# eVV_Main_Controller.net
KiCad netlist of a schematic drawn in Altium Designer
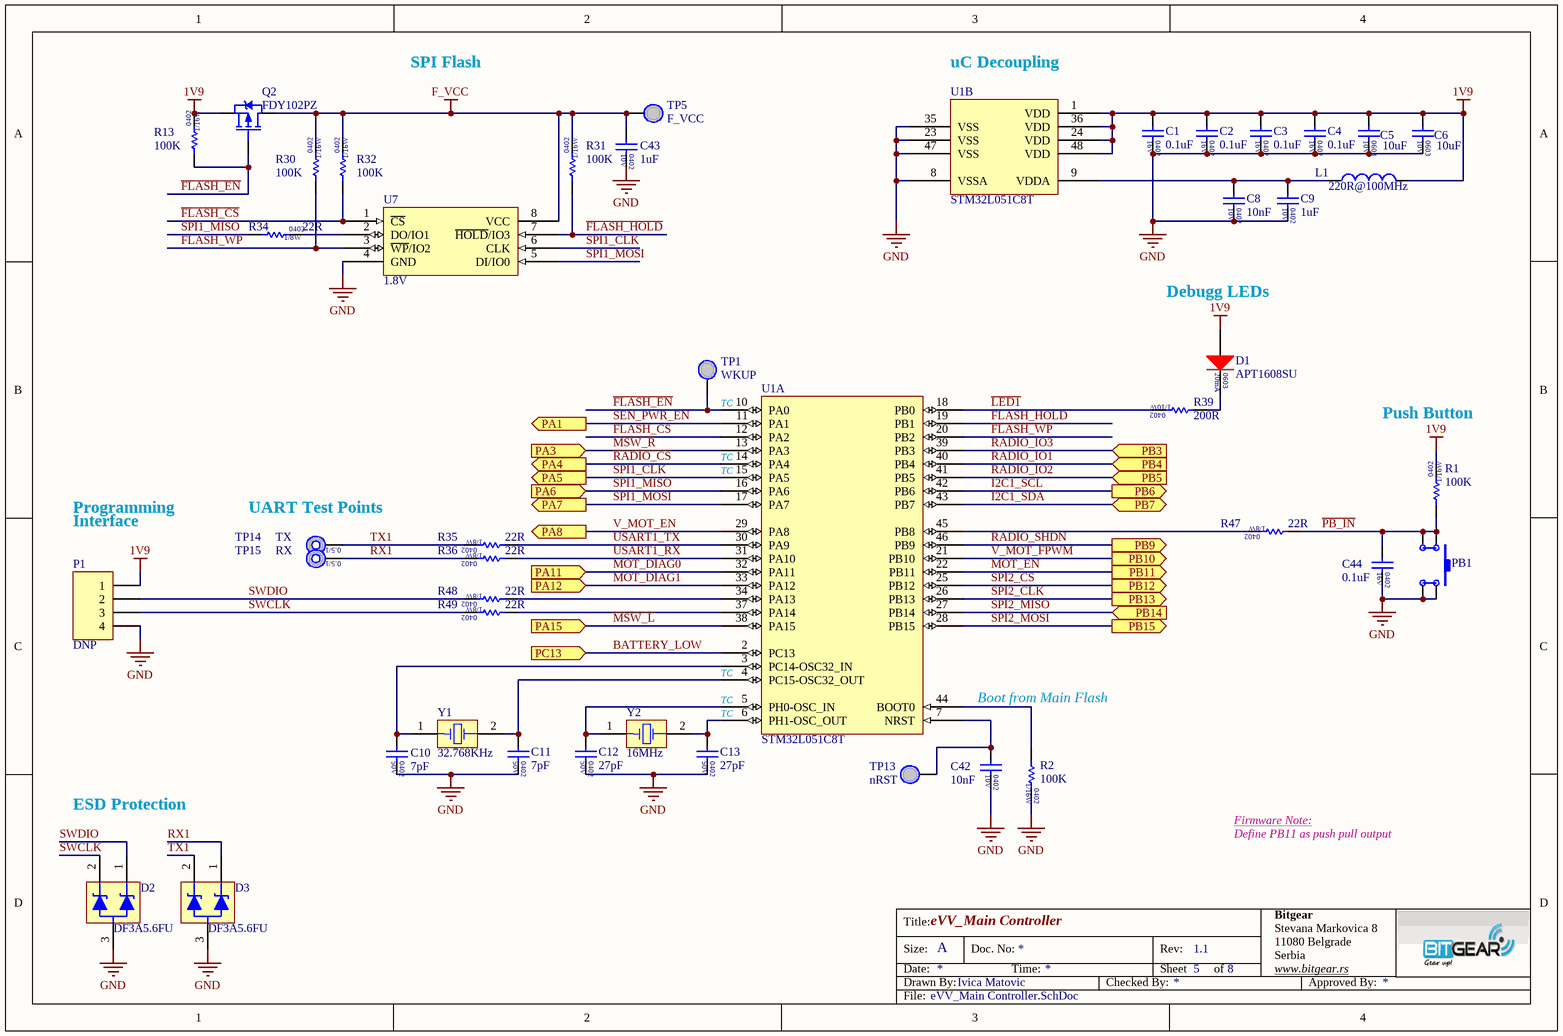
[diagram p0: eVV_Main Controller.SchDoc]

(export (version "E")
  (design (tool "Eeschema 10.0.6"))
  (components
    (comp (ref "C1")
      (value "0.1uF")
      (footprint "CAPC1005X60N")
      (description "CAP CER 0.1UF 0402 (1005) 16V X7R 10%")
      (fields (field (name "MANUFACTURER") "Murata Electronics North America"))
      (libsource (lib "ecoVENTV") (part "Cap-1005 (0402) CER 0.1UF 16V X7R 10%"))
    )
    (comp (ref "C2")
      (value "0.1uF")
      (footprint "CAPC1005X60N")
      (description "CAP CER 0.1UF 0402 (1005) 16V X7R 10%")
      (fields (field (name "MANUFACTURER") "Murata Electronics North America"))
      (libsource (lib "ecoVENTV") (part "Cap-1005 (0402) CER 0.1UF 16V X7R 10%"))
    )
    (comp (ref "C3")
      (value "0.1uF")
      (footprint "CAPC1005X60N")
      (description "CAP CER 0.1UF 0402 (1005) 16V X7R 10%")
      (fields (field (name "MANUFACTURER") "Murata Electronics North America"))
      (libsource (lib "ecoVENTV") (part "Cap-1005 (0402) CER 0.1UF 16V X7R 10%"))
    )
    (comp (ref "C4")
      (value "0.1uF")
      (footprint "CAPC1005X60N")
      (description "CAP CER 0.1UF 0402 (1005) 16V X7R 10%")
      (fields (field (name "MANUFACTURER") "Murata Electronics North America"))
      (libsource (lib "ecoVENTV") (part "Cap-1005 (0402) CER 0.1UF 16V X7R 10%"))
    )
    (comp (ref "C5")
      (value "10uF")
      (footprint "CAPC1608X95N")
      (description "Capacitor Ceramic 10uF 1608 (0603) 10V X5R 20%")
      (fields (field (name "MANUFACTURER") "Taiyo Yuden"))
      (libsource (lib "ecoVENTV") (part "Cap-1608 (0603) CER 10uF 10V X5R 20%"))
    )
    (comp (ref "C6")
      (value "10uF")
      (footprint "CAPC1608X95N")
      (description "Capacitor Ceramic 10uF 1608 (0603) 10V X5R 20%")
      (fields (field (name "MANUFACTURER") "Taiyo Yuden"))
      (libsource (lib "ecoVENTV") (part "Cap-1608 (0603) CER 10uF 10V X5R 20%"))
    )
    (comp (ref "C8")
      (value "10nF")
      (footprint "CAPC1005X60N")
      (description "Cap-1005 (0402) CER 10nF 10V X7R 10%")
      (fields (field (name "MANUFACTURER") "Samsung"))
      (libsource (lib "ecoVENTV") (part "Cap-1005 (0402) CER 10nF 10V X7R 10%"))
    )
    (comp (ref "C9")
      (value "1uF")
      (footprint "CAPC1005X60N")
      (description "Cap-1005 (0402) CER 1uF 10V X5R 10%")
      (fields (field (name "MANUFACTURER") "Murata Electronics North America"))
      (libsource (lib "ecoVENTV") (part "Cap-1005 (0402) CER 1uF 10V X5R 10%"))
    )
    (comp (ref "C10")
      (value "7pF")
      (footprint "CAPC1005X60N")
      (description "Cap-1005 (0402) CER 7pF 50V C0G 0.5pF")
      (fields (field (name "MANUFACTURER") "Murata Electronics North America"))
      (libsource (lib "ecoVENTV") (part "Cap-1005 (0402) CER 7pF 50V C0G 0.5pF"))
    )
    (comp (ref "C11")
      (value "7pF")
      (footprint "CAPC1005X60N")
      (description "Cap-1005 (0402) CER 7pF 50V C0G 0.5pF")
      (fields (field (name "MANUFACTURER") "Murata Electronics North America"))
      (libsource (lib "ecoVENTV") (part "Cap-1005 (0402) CER 7pF 50V C0G 0.5pF"))
    )
    (comp (ref "C12")
      (value "27pF")
      (footprint "CAPC1005X60N")
      (description "CAP CER 27PF 50V 5% NP0 0402 (1005)")
      (fields (field (name "MANUFACTURER") "Murata Electronics North America"))
      (libsource (lib "ecoVENTV") (part "Cap-1005 (0402) CER 27pF 50V NP0 5%"))
    )
    (comp (ref "C13")
      (value "27pF")
      (footprint "CAPC1005X60N")
      (description "CAP CER 27PF 50V 5% NP0 0402 (1005)")
      (fields (field (name "MANUFACTURER") "Murata Electronics North America"))
      (libsource (lib "ecoVENTV") (part "Cap-1005 (0402) CER 27pF 50V NP0 5%"))
    )
    (comp (ref "C42")
      (value "10nF")
      (footprint "CAPC1005X60N")
      (description "Cap-1005 (0402) CER 10nF 10V X7R 10%")
      (fields (field (name "MANUFACTURER") "Samsung"))
      (libsource (lib "ecoVENTV") (part "Cap-1005 (0402) CER 10nF 10V X7R 10%"))
    )
    (comp (ref "C43")
      (value "1uF")
      (footprint "CAPC1005X60N")
      (description "Cap-1005 (0402) CER 1uF 10V X5R 10%")
      (fields (field (name "MANUFACTURER") "Murata Electronics North America"))
      (libsource (lib "ecoVENTV") (part "Cap-1005 (0402) CER 1uF 10V X5R 10%"))
    )
    (comp (ref "C44")
      (value "0.1uF")
      (footprint "CAPC1005X60N")
      (description "CAP CER 0.1UF 0402 (1005) 16V X7R 10%")
      (fields (field (name "MANUFACTURER") "Murata Electronics North America"))
      (libsource (lib "ecoVENTV") (part "Cap-1005 (0402) CER 0.1UF 16V X7R 10%"))
    )
    (comp (ref "D1")
      (value "APT1608SU")
      (footprint "DIOC1608X84N_R")
      (description "LED Red 0603 20mA")
      (fields (field (name "MANUFACTURER") "Kingbright"))
      (libsource (lib "ecoVENTV") (part "APT1608SU"))
    )
    (comp (ref "D2")
      (value "DF3A5.6FU")
      (footprint "SOT65P210X110-3N")
      (description "30kV ESD Protection Diode, Vr=2.5V, Vz=5.6V, Ilkg=1uA")
      (fields (field (name "MANUFACTURER") "Toshiba Semiconductor"))
      (libsource (lib "ecoVENTV") (part "DF3A5.6FU"))
    )
    (comp (ref "D3")
      (value "DF3A5.6FU")
      (footprint "SOT65P210X110-3N")
      (description "30kV ESD Protection Diode, Vr=2.5V, Vz=5.6V, Ilkg=1uA")
      (fields (field (name "MANUFACTURER") "Toshiba Semiconductor"))
      (libsource (lib "ecoVENTV") (part "DF3A5.6FU"))
    )
    (comp (ref "L1")
      (value "220R@100MHz")
      (footprint "INDC1005X60N")
      (description "FERRITE BEAD 220 Ohm 800mA 0402")
      (fields (field (name "MANUFACTURER") "Taiyo Yuden"))
      (libsource (lib "ecoVENTV") (part "FBead-1005 (0402) 220 Ohm 800mA"))
    )
    (comp (ref "P1")
      (value "DNP")
      (footprint "HDR1X4_100MIL")
      (description "Header, 4-Pin")
      (libsource (lib "ecoVENTV") (part "Header 4"))
    )
    (comp (ref "PB1")
      (value "switch")
      (footprint "CK_KMR221NG")
      (description "Push Button SPST-NO 4.6X2.8mm")
      (fields (field (name "MANUFACTURER") "C&K Components"))
      (libsource (lib "ecoVENTV") (part "KMR221NG"))
    )
    (comp (ref "Q2")
      (value "FDY102PZ")
      (footprint "SOT50P160X78-3N")
      (description "P-MOSFET Single 0.83A Low Vgs")
      (fields (field (name "MANUFACTURER") "Fairchild"))
      (libsource (lib "ecoVENTV") (part "FDY102PZ"))
    )
    (comp (ref "R1")
      (value "100K")
      (footprint "RESC1005X40AN")
      (description "Res-1005 (0402) 100 KOhm 1/16W 1%")
      (fields (field (name "MANUFACTURER") "Vishay Dale"))
      (libsource (lib "ecoVENTV") (part "Res-1005 (0402) 100 KOhm 1/16W 1%"))
    )
    (comp (ref "R2")
      (value "100K")
      (footprint "RESC1005X40AN")
      (description "Res-1005 (0402) 100 KOhm 1/16W 1%")
      (fields (field (name "MANUFACTURER") "Vishay Dale"))
      (libsource (lib "ecoVENTV") (part "Res-1005 (0402) 100 KOhm 1/16W 1%"))
    )
    (comp (ref "R13")
      (value "100K")
      (footprint "RESC1005X40AN")
      (description "Res-1005 (0402) 100 KOhm 1/16W 1%")
      (fields (field (name "MANUFACTURER") "Vishay Dale"))
      (libsource (lib "ecoVENTV") (part "Res-1005 (0402) 100 KOhm 1/16W 1%"))
    )
    (comp (ref "R30")
      (value "100K")
      (footprint "RESC1005X40AN")
      (description "Res-1005 (0402) 100 KOhm 1/16W 1%")
      (fields (field (name "MANUFACTURER") "Vishay Dale"))
      (libsource (lib "ecoVENTV") (part "Res-1005 (0402) 100 KOhm 1/16W 1%"))
    )
    (comp (ref "R31")
      (value "100K")
      (footprint "RESC1005X40AN")
      (description "Res-1005 (0402) 100 KOhm 1/16W 1%")
      (fields (field (name "MANUFACTURER") "Vishay Dale"))
      (libsource (lib "ecoVENTV") (part "Res-1005 (0402) 100 KOhm 1/16W 1%"))
    )
    (comp (ref "R32")
      (value "100K")
      (footprint "RESC1005X40AN")
      (description "Res-1005 (0402) 100 KOhm 1/16W 1%")
      (fields (field (name "MANUFACTURER") "Vishay Dale"))
      (libsource (lib "ecoVENTV") (part "Res-1005 (0402) 100 KOhm 1/16W 1%"))
    )
    (comp (ref "R34")
      (value "22R")
      (footprint "RESC1005X40AN")
      (description "Res-1005 (0402) 22 Ohm 1/8W 1%")
      (fields (field (name "MANUFACTURER") "Vishay Dale"))
      (libsource (lib "ecoVENTV") (part "Res-1005 (0402) 22 Ohm 1/8W 1%"))
    )
    (comp (ref "R35")
      (value "22R")
      (footprint "RESC1005X40AN")
      (description "Res-1005 (0402) 22 Ohm 1/8W 1%")
      (fields (field (name "MANUFACTURER") "Vishay Dale"))
      (libsource (lib "ecoVENTV") (part "Res-1005 (0402) 22 Ohm 1/8W 1%"))
    )
    (comp (ref "R36")
      (value "22R")
      (footprint "RESC1005X40AN")
      (description "Res-1005 (0402) 22 Ohm 1/8W 1%")
      (fields (field (name "MANUFACTURER") "Vishay Dale"))
      (libsource (lib "ecoVENTV") (part "Res-1005 (0402) 22 Ohm 1/8W 1%"))
    )
    (comp (ref "R39")
      (value "200R")
      (footprint "RESC1005X40AN")
      (description "Res-1005 (0402) 200 Ohm 1/10W 5%")
      (fields (field (name "MANUFACTURER") "Vishay Dale"))
      (libsource (lib "ecoVENTV") (part "Res-1005 (0402) 200 Ohm 1/10W 5%"))
    )
    (comp (ref "R47")
      (value "22R")
      (footprint "RESC1005X40AN")
      (description "Res-1005 (0402) 22 Ohm 1/8W 1%")
      (fields (field (name "MANUFACTURER") "Vishay Dale"))
      (libsource (lib "ecoVENTV") (part "Res-1005 (0402) 22 Ohm 1/8W 1%"))
    )
    (comp (ref "R48")
      (value "22R")
      (footprint "RESC1005X40AN")
      (description "Res-1005 (0402) 22 Ohm 1/8W 1%")
      (fields (field (name "MANUFACTURER") "Vishay Dale"))
      (libsource (lib "ecoVENTV") (part "Res-1005 (0402) 22 Ohm 1/8W 1%"))
    )
    (comp (ref "R49")
      (value "22R")
      (footprint "RESC1005X40AN")
      (description "Res-1005 (0402) 22 Ohm 1/8W 1%")
      (fields (field (name "MANUFACTURER") "Vishay Dale"))
      (libsource (lib "ecoVENTV") (part "Res-1005 (0402) 22 Ohm 1/8W 1%"))
    )
    (comp (ref "TP1")
      (value "WKUP")
      (footprint "TEST_POINT_1MM")
      (description "Test point")
      (libsource (lib "ecoVENTV") (part "TP"))
    )
    (comp (ref "TP5")
      (value "F_VCC")
      (footprint "TEST_POINT_1MM")
      (description "Test point")
      (libsource (lib "") (part "TP_2"))
    )
    (comp (ref "TP13")
      (value "nRST")
      (footprint "TEST_POINT_1MM")
      (description "Test point")
      (libsource (lib "") (part "TP_1"))
    )
    (comp (ref "TP14")
      (value "TX")
      (footprint "TEST_POINT_TH_1MM")
      (description "Test point Through Hole")
      (libsource (lib "ecoVENTV") (part "TP TH"))
    )
    (comp (ref "TP15")
      (value "RX")
      (footprint "TEST_POINT_TH_1MM")
      (description "Test point Through Hole")
      (libsource (lib "ecoVENTV") (part "TP TH"))
    )
    (comp (ref "U1")
      (value "STM32L051C8T")
      (footprint "QFP50P900X900X160-48N")
      (description "48-Pin, Access line, ultra-low-power, 32-bit MCU")
      (fields (field (name "MANUFACTURER") "ST Microelectronics"))
      (libsource (lib "ecoVENTV") (part "STM32L051C8T"))
    )
    (comp (ref "U7")
      (value "1.8V")
      (footprint "SOIC127P600X175-8N")
      (description "SPI Flash 8Mbit 1.8V 7uA sleep current")
      (fields (field (name "MANUFACTURER") "Winbond Electronics"))
      (libsource (lib "ecoVENTV") (part "W25Q80BW"))
    )
    (comp (ref "Y1")
      (value "32.768KHz")
      (footprint "ABS07")
      (description "Crystal 32.768KHZ 3.2mm x 1.5 mm 7pF")
      (fields (field (name "MANUFACTURER") "Abracon Corporation"))
      (libsource (lib "ecoVENTV") (part "ABS07-32.768KHz 7pF"))
    )
    (comp (ref "Y2")
      (value "16MHz")
      (footprint "ABM3")
      (description "Crystal Oscillator 16MHz 5.0X3.2mm")
      (fields (field (name "MANUFACTURER") "Abracon"))
      (libsource (lib "ecoVENTV") (part "ABM3-16.000"))
    )
  )
  (nets
    (net (code "1") (name "/BATTERY_LOW") (class "Default")
      (node (ref "U1") (pin "2") (pinfunction "PC13_2") (pintype "bidirectional"))
    )
    (net (code "2") (name "/I2C1_SCL") (class "Default")
      (node (ref "U1") (pin "42") (pinfunction "PB6_42") (pintype "bidirectional"))
    )
    (net (code "3") (name "/I2C1_SDA") (class "Default")
      (node (ref "U1") (pin "43") (pinfunction "PB7_43") (pintype "bidirectional"))
    )
    (net (code "4") (name "/LED1") (class "Default")
      (node (ref "R39") (pin "1") (pinfunction "1_1") (pintype "passive"))
      (node (ref "U1") (pin "18") (pinfunction "PB0_18") (pintype "bidirectional"))
    )
    (net (code "5") (name "/MOT_DIAG0") (class "Default")
      (node (ref "U1") (pin "32") (pinfunction "PA11_32") (pintype "bidirectional"))
    )
    (net (code "6") (name "/MOT_DIAG1") (class "Default")
      (node (ref "U1") (pin "33") (pinfunction "PA12_33") (pintype "bidirectional"))
    )
    (net (code "7") (name "/MOT_EN") (class "Default")
      (node (ref "U1") (pin "22") (pinfunction "PB11_22") (pintype "bidirectional"))
    )
    (net (code "8") (name "/MSW_L") (class "Default")
      (node (ref "U1") (pin "38") (pinfunction "PA15_38") (pintype "bidirectional"))
    )
    (net (code "9") (name "/MSW_R") (class "Default")
      (node (ref "U1") (pin "13") (pinfunction "PA3_13") (pintype "bidirectional"))
    )
    (net (code "10") (name "/PB_IN") (class "Default")
      (node (ref "C44") (pin "1") (pinfunction "1_1") (pintype "passive"))
      (node (ref "PB1") (pin "1") (pinfunction "1_1") (pintype "passive"))
      (node (ref "PB1") (pin "2") (pinfunction "2_2") (pintype "passive"))
      (node (ref "R1") (pin "2") (pinfunction "2_2") (pintype "passive"))
      (node (ref "R47") (pin "2") (pinfunction "2_2") (pintype "passive"))
    )
    (net (code "11") (name "/RADIO_IO1") (class "Default")
      (node (ref "U1") (pin "40") (pinfunction "PB4_40") (pintype "bidirectional"))
    )
    (net (code "12") (name "/RADIO_IO2") (class "Default")
      (node (ref "U1") (pin "41") (pinfunction "PB5_41") (pintype "bidirectional"))
    )
    (net (code "13") (name "/RADIO_IO3") (class "Default")
      (node (ref "U1") (pin "39") (pinfunction "PB3_39") (pintype "bidirectional"))
    )
    (net (code "14") (name "/RADIO_SHDN") (class "Default")
      (node (ref "U1") (pin "46") (pinfunction "PB9_46") (pintype "bidirectional"))
    )
    (net (code "15") (name "/RX1") (class "Default")
      (node (ref "D3") (pin "1") (pinfunction "C1_1") (pintype "passive"))
      (node (ref "R36") (pin "1") (pinfunction "1_1") (pintype "passive"))
      (node (ref "TP15") (pin "1") (pinfunction "1_1") (pintype "passive"))
    )
    (net (code "16") (name "/SEN_PWR_EN") (class "Default")
      (node (ref "U1") (pin "11") (pinfunction "PA1_11") (pintype "bidirectional"))
    )
    (net (code "17") (name "/SPI1_CLK") (class "Default")
      (node (ref "U1") (pin "15") (pinfunction "PA5_15") (pintype "bidirectional"))
      (node (ref "U7") (pin "6") (pinfunction "CLK_6") (pintype "input"))
    )
    (net (code "18") (name "/SPI1_MISO") (class "Default")
      (node (ref "R34") (pin "2") (pinfunction "2_2") (pintype "passive"))
      (node (ref "U1") (pin "16") (pinfunction "PA6_16") (pintype "bidirectional"))
    )
    (net (code "19") (name "/SPI1_MOSI") (class "Default")
      (node (ref "U1") (pin "17") (pinfunction "PA7_17") (pintype "bidirectional"))
      (node (ref "U7") (pin "5") (pinfunction "DI/IO0_5") (pintype "input"))
    )
    (net (code "20") (name "/SPI2_CLK") (class "Default")
      (node (ref "U1") (pin "26") (pinfunction "PB13_26") (pintype "bidirectional"))
    )
    (net (code "21") (name "/SPI2_CS") (class "Default")
      (node (ref "U1") (pin "25") (pinfunction "PB12_25") (pintype "bidirectional"))
    )
    (net (code "22") (name "/SPI2_MISO") (class "Default")
      (node (ref "U1") (pin "27") (pinfunction "PB14_27") (pintype "bidirectional"))
    )
    (net (code "23") (name "/SPI2_MOSI") (class "Default")
      (node (ref "U1") (pin "28") (pinfunction "PB15_28") (pintype "bidirectional"))
    )
    (net (code "24") (name "/SWCLK") (class "Default")
      (node (ref "D2") (pin "2") (pinfunction "C2_2") (pintype "passive"))
      (node (ref "P1") (pin "3") (pinfunction "3_3") (pintype "passive"))
      (node (ref "R49") (pin "1") (pinfunction "1_1") (pintype "passive"))
    )
    (net (code "25") (name "/SWDIO") (class "Default")
      (node (ref "D2") (pin "1") (pinfunction "C1_1") (pintype "passive"))
      (node (ref "P1") (pin "2") (pinfunction "2_2") (pintype "passive"))
      (node (ref "R48") (pin "1") (pinfunction "1_1") (pintype "passive"))
    )
    (net (code "26") (name "/TX1") (class "Default")
      (node (ref "D3") (pin "2") (pinfunction "C2_2") (pintype "passive"))
      (node (ref "R35") (pin "1") (pinfunction "1_1") (pintype "passive"))
      (node (ref "TP14") (pin "1") (pinfunction "1_1") (pintype "passive"))
    )
    (net (code "27") (name "/USART1_RX") (class "Default")
      (node (ref "R36") (pin "2") (pinfunction "2_2") (pintype "passive"))
      (node (ref "U1") (pin "31") (pinfunction "PA10_31") (pintype "bidirectional"))
    )
    (net (code "28") (name "/USART1_TX") (class "Default")
      (node (ref "R35") (pin "2") (pinfunction "2_2") (pintype "passive"))
      (node (ref "U1") (pin "30") (pinfunction "PA9_30") (pintype "bidirectional"))
    )
    (net (code "29") (name "/V_MOT_EN") (class "Default")
      (node (ref "U1") (pin "29") (pinfunction "PA8_29") (pintype "bidirectional"))
    )
    (net (code "30") (name "/V_MOT_FPWM") (class "Default")
      (node (ref "U1") (pin "21") (pinfunction "PB10_21") (pintype "bidirectional"))
    )
    (net (code "31") (name "/~{FLASH_CS}") (class "Default")
      (node (ref "R32") (pin "2") (pinfunction "2_2") (pintype "passive"))
      (node (ref "U1") (pin "12") (pinfunction "PA2_12") (pintype "bidirectional"))
      (node (ref "U7") (pin "1") (pinfunction "~{CS}_1") (pintype "input"))
    )
    (net (code "32") (name "/~{FLASH_EN}") (class "Default")
      (node (ref "Q2") (pin "1") (pinfunction "G_1") (pintype "passive"))
      (node (ref "R13") (pin "2") (pinfunction "2_2") (pintype "passive"))
      (node (ref "TP1") (pin "1") (pinfunction "1_1") (pintype "passive"))
      (node (ref "U1") (pin "10") (pinfunction "PA0_10") (pintype "bidirectional"))
    )
    (net (code "33") (name "/~{FLASH_HOLD}") (class "Default")
      (node (ref "R31") (pin "2") (pinfunction "2_2") (pintype "passive"))
      (node (ref "U1") (pin "19") (pinfunction "PB1_19") (pintype "bidirectional"))
      (node (ref "U7") (pin "7") (pinfunction "~{HOLD}/IO3_7") (pintype "input"))
    )
    (net (code "34") (name "/~{FLASH_WP}") (class "Default")
      (node (ref "R30") (pin "2") (pinfunction "2_2") (pintype "passive"))
      (node (ref "U1") (pin "20") (pinfunction "PB2_20") (pintype "bidirectional"))
      (node (ref "U7") (pin "3") (pinfunction "~{WP}/IO2_3") (pintype "bidirectional"))
    )
    (net (code "35") (name "/~{RADIO_CS}") (class "Default")
      (node (ref "U1") (pin "14") (pinfunction "PA4_14") (pintype "bidirectional"))
    )
    (net (code "36") (name "1V9") (class "Default")
      (node (ref "C1") (pin "1") (pinfunction "1_1") (pintype "passive"))
      (node (ref "C2") (pin "1") (pinfunction "1_1") (pintype "passive"))
      (node (ref "C3") (pin "1") (pinfunction "1_1") (pintype "passive"))
      (node (ref "C4") (pin "1") (pinfunction "1_1") (pintype "passive"))
      (node (ref "C5") (pin "1") (pinfunction "1_1") (pintype "passive"))
      (node (ref "C6") (pin "1") (pinfunction "1_1") (pintype "passive"))
      (node (ref "D1") (pin "1") (pinfunction "A_1") (pintype "passive"))
      (node (ref "L1") (pin "2") (pinfunction "2_2") (pintype "passive"))
      (node (ref "P1") (pin "1") (pinfunction "1_1") (pintype "passive"))
      (node (ref "Q2") (pin "2") (pinfunction "S_2") (pintype "passive"))
      (node (ref "R1") (pin "1") (pinfunction "1_1") (pintype "passive"))
      (node (ref "R13") (pin "1") (pinfunction "1_1") (pintype "passive"))
      (node (ref "U1") (pin "1") (pinfunction "VDD_1") (pintype "power_in"))
      (node (ref "U1") (pin "24") (pinfunction "VDD_24") (pintype "power_in"))
      (node (ref "U1") (pin "36") (pinfunction "VDD_36") (pintype "power_in"))
      (node (ref "U1") (pin "48") (pinfunction "VDD_48") (pintype "power_in"))
    )
    (net (code "37") (name "F_VCC") (class "Default")
      (node (ref "C43") (pin "1") (pinfunction "1_1") (pintype "passive"))
      (node (ref "Q2") (pin "3") (pinfunction "D_3") (pintype "passive"))
      (node (ref "R30") (pin "1") (pinfunction "1_1") (pintype "passive"))
      (node (ref "R31") (pin "1") (pinfunction "1_1") (pintype "passive"))
      (node (ref "R32") (pin "1") (pinfunction "1_1") (pintype "passive"))
      (node (ref "TP5") (pin "1") (pinfunction "1_1") (pintype "passive"))
      (node (ref "U7") (pin "8") (pinfunction "VCC_8") (pintype "power_in"))
    )
    (net (code "38") (name "GND") (class "Default")
      (node (ref "C1") (pin "2") (pinfunction "2_2") (pintype "passive"))
      (node (ref "C10") (pin "2") (pinfunction "2_2") (pintype "passive"))
      (node (ref "C11") (pin "2") (pinfunction "2_2") (pintype "passive"))
      (node (ref "C12") (pin "2") (pinfunction "2_2") (pintype "passive"))
      (node (ref "C13") (pin "2") (pinfunction "2_2") (pintype "passive"))
      (node (ref "C2") (pin "2") (pinfunction "2_2") (pintype "passive"))
      (node (ref "C3") (pin "2") (pinfunction "2_2") (pintype "passive"))
      (node (ref "C4") (pin "2") (pinfunction "2_2") (pintype "passive"))
      (node (ref "C42") (pin "2") (pinfunction "2_2") (pintype "passive"))
      (node (ref "C43") (pin "2") (pinfunction "2_2") (pintype "passive"))
      (node (ref "C44") (pin "2") (pinfunction "2_2") (pintype "passive"))
      (node (ref "C5") (pin "2") (pinfunction "2_2") (pintype "passive"))
      (node (ref "C6") (pin "2") (pinfunction "2_2") (pintype "passive"))
      (node (ref "C8") (pin "2") (pinfunction "2_2") (pintype "passive"))
      (node (ref "C9") (pin "2") (pinfunction "2_2") (pintype "passive"))
      (node (ref "D2") (pin "3") (pinfunction "A_3") (pintype "passive"))
      (node (ref "D3") (pin "3") (pinfunction "A_3") (pintype "passive"))
      (node (ref "P1") (pin "4") (pinfunction "4_4") (pintype "passive"))
      (node (ref "PB1") (pin "3") (pinfunction "3_3") (pintype "passive"))
      (node (ref "PB1") (pin "4") (pinfunction "4_4") (pintype "passive"))
      (node (ref "R2") (pin "1") (pinfunction "1_1") (pintype "passive"))
      (node (ref "U1") (pin "23") (pinfunction "VSS_23") (pintype "power_in"))
      (node (ref "U1") (pin "35") (pinfunction "VSS_35") (pintype "power_in"))
      (node (ref "U1") (pin "47") (pinfunction "VSS_47") (pintype "power_in"))
      (node (ref "U1") (pin "8") (pinfunction "VSSA_8") (pintype "power_in"))
      (node (ref "U7") (pin "4") (pinfunction "GND_4") (pintype "power_in"))
    )
    (net (code "39") (name "Net-(D1-C)") (class "Default")
      (node (ref "D1") (pin "2") (pinfunction "C_2") (pintype "passive"))
      (node (ref "R39") (pin "2") (pinfunction "2_2") (pintype "passive"))
    )
    (net (code "40") (name "Net-(U1A-BOOT0)") (class "Default")
      (node (ref "R2") (pin "2") (pinfunction "2_2") (pintype "passive"))
      (node (ref "U1") (pin "44") (pinfunction "BOOT0_44") (pintype "input"))
    )
    (net (code "41") (name "Net-(U1A-NRST)") (class "Default")
      (node (ref "C42") (pin "1") (pinfunction "1_1") (pintype "passive"))
      (node (ref "TP13") (pin "1") (pinfunction "1_1") (pintype "passive"))
      (node (ref "U1") (pin "7") (pinfunction "NRST_7") (pintype "input"))
    )
    (net (code "42") (name "Net-(U1A-PA13)") (class "Default")
      (node (ref "R48") (pin "2") (pinfunction "2_2") (pintype "passive"))
      (node (ref "U1") (pin "34") (pinfunction "PA13_34") (pintype "bidirectional"))
    )
    (net (code "43") (name "Net-(U1A-PA14)") (class "Default")
      (node (ref "R49") (pin "2") (pinfunction "2_2") (pintype "passive"))
      (node (ref "U1") (pin "37") (pinfunction "PA14_37") (pintype "bidirectional"))
    )
    (net (code "44") (name "Net-(U1A-PB8)") (class "Default")
      (node (ref "R47") (pin "1") (pinfunction "1_1") (pintype "passive"))
      (node (ref "U1") (pin "45") (pinfunction "PB8_45") (pintype "bidirectional"))
    )
    (net (code "45") (name "Net-(U1A-PC14-OSC32_IN)") (class "Default")
      (node (ref "C10") (pin "1") (pinfunction "1_1") (pintype "passive"))
      (node (ref "U1") (pin "3") (pinfunction "PC14-OSC32_IN_3") (pintype "bidirectional"))
      (node (ref "Y1") (pin "1") (pinfunction "OSC1_1") (pintype "passive"))
    )
    (net (code "46") (name "Net-(U1A-PC15-OSC32_OUT)") (class "Default")
      (node (ref "C11") (pin "1") (pinfunction "1_1") (pintype "passive"))
      (node (ref "U1") (pin "4") (pinfunction "PC15-OSC32_OUT_4") (pintype "bidirectional"))
      (node (ref "Y1") (pin "2") (pinfunction "COM_2") (pintype "passive"))
    )
    (net (code "47") (name "Net-(U1A-PH0-OSC_IN)") (class "Default")
      (node (ref "C12") (pin "1") (pinfunction "1_1") (pintype "passive"))
      (node (ref "U1") (pin "5") (pinfunction "PH0-OSC_IN_5") (pintype "bidirectional"))
      (node (ref "Y2") (pin "1") (pinfunction "OSC1_1") (pintype "passive"))
    )
    (net (code "48") (name "Net-(U1A-PH1-OSC_OUT)") (class "Default")
      (node (ref "C13") (pin "1") (pinfunction "1_1") (pintype "passive"))
      (node (ref "U1") (pin "6") (pinfunction "PH1-OSC_OUT_6") (pintype "bidirectional"))
      (node (ref "Y2") (pin "2") (pinfunction "COM_2") (pintype "passive"))
    )
    (net (code "49") (name "Net-(U1B-VDDA)") (class "Default")
      (node (ref "C8") (pin "1") (pinfunction "1_1") (pintype "passive"))
      (node (ref "C9") (pin "1") (pinfunction "1_1") (pintype "passive"))
      (node (ref "L1") (pin "1") (pinfunction "1_1") (pintype "passive"))
      (node (ref "U1") (pin "9") (pinfunction "VDDA_9") (pintype "power_in"))
    )
    (net (code "50") (name "Net-(U7-DO{slash}IO1)") (class "Default")
      (node (ref "R34") (pin "1") (pinfunction "1_1") (pintype "passive"))
      (node (ref "U7") (pin "2") (pinfunction "DO/IO1_2") (pintype "bidirectional"))
    )
  )
)
